# kilafors_rev_A.net
KiCad netlist of a schematic drawn in EAGLE
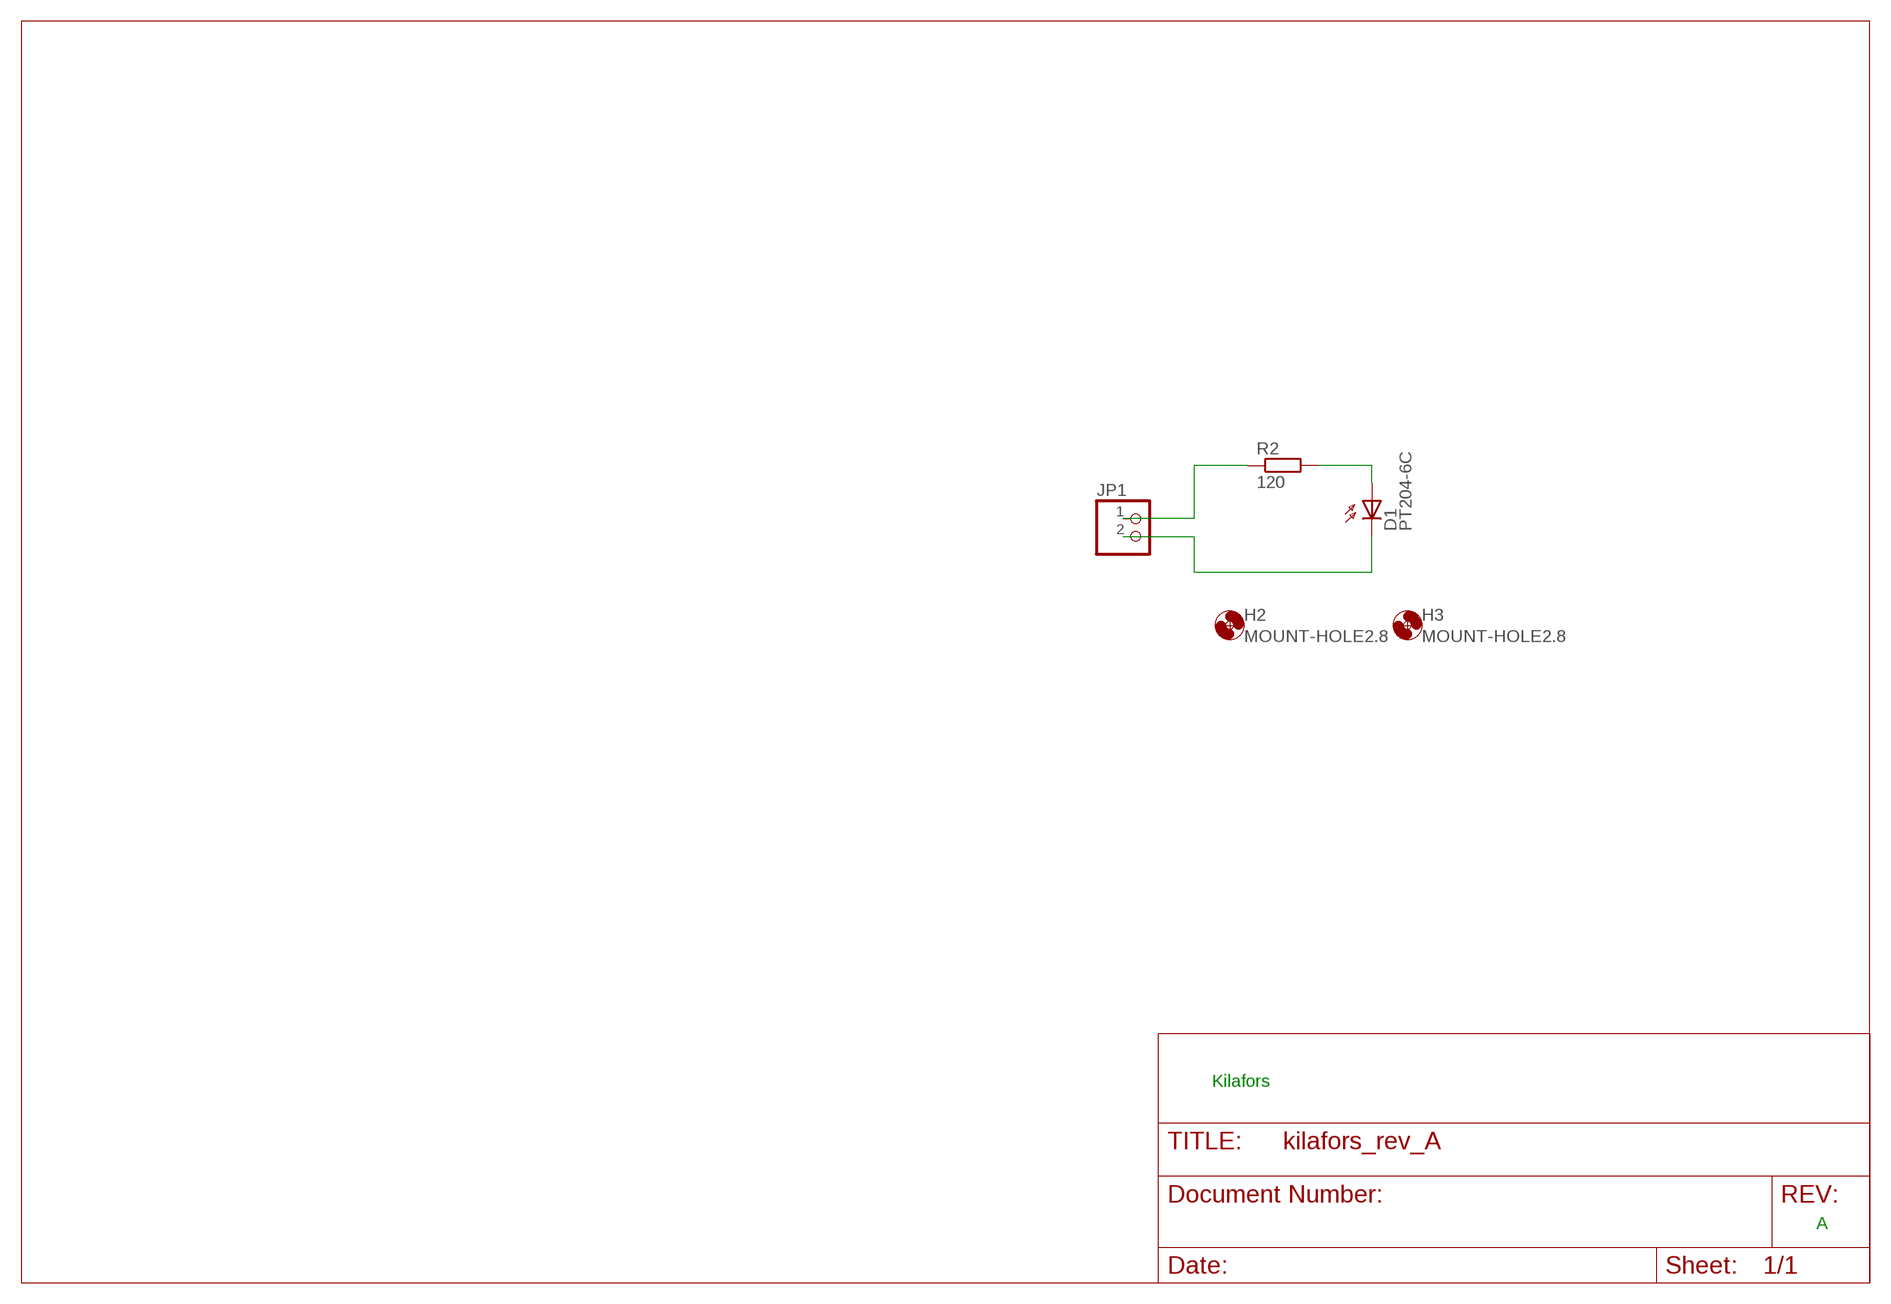
[diagram p0: schematic, sheet 1]

(export (version "E")
  (design (tool "Eeschema 10.0.6"))
  (components
    (comp (ref "D1")
      (value "PT204-6C")
      (footprint "eagle-import:BPW32")
      (libsource (lib "eagle-import") (part "BPW32"))
    )
    (comp (ref "H2")
      (value "MOUNT-HOLE2.8")
      (footprint "eagle-import:2,8")
      (libsource (lib "eagle-import") (part "MOUNT-HOLE2.8"))
    )
    (comp (ref "H3")
      (value "MOUNT-HOLE2.8")
      (footprint "eagle-import:2,8")
      (libsource (lib "eagle-import") (part "MOUNT-HOLE2.8"))
    )
    (comp (ref "JP1")
      (value "PINHD-1X2")
      (footprint "eagle-import:1X02")
      (libsource (lib "eagle-import") (part "PINHD-1X2"))
    )
    (comp (ref "R2")
      (value "120")
      (footprint "eagle-import:0204_5")
      (libsource (lib "eagle-import") (part "R-EU_0204/5"))
    )
  )
  (nets
    (net (code "1") (name "Net-(D1-C)") (class "Default")
      (node (ref "D1") (pin "K") (pinfunction "C_K") (pintype "passive"))
      (node (ref "JP1") (pin "2") (pinfunction "2_2") (pintype "passive"))
    )
    (net (code "2") (name "Net-(D1-PadA)") (class "Default")
      (node (ref "D1") (pin "A") (pinfunction "A_A") (pintype "passive"))
      (node (ref "R2") (pin "2") (pinfunction "2_2") (pintype "passive"))
    )
    (net (code "3") (name "Net-(JP1-Pad1)") (class "Default")
      (node (ref "JP1") (pin "1") (pinfunction "1_1") (pintype "passive"))
      (node (ref "R2") (pin "1") (pinfunction "1_1") (pintype "passive"))
    )
  )
)
